# Separator-C.net
KiCad netlist of a schematic drawn in EAGLE
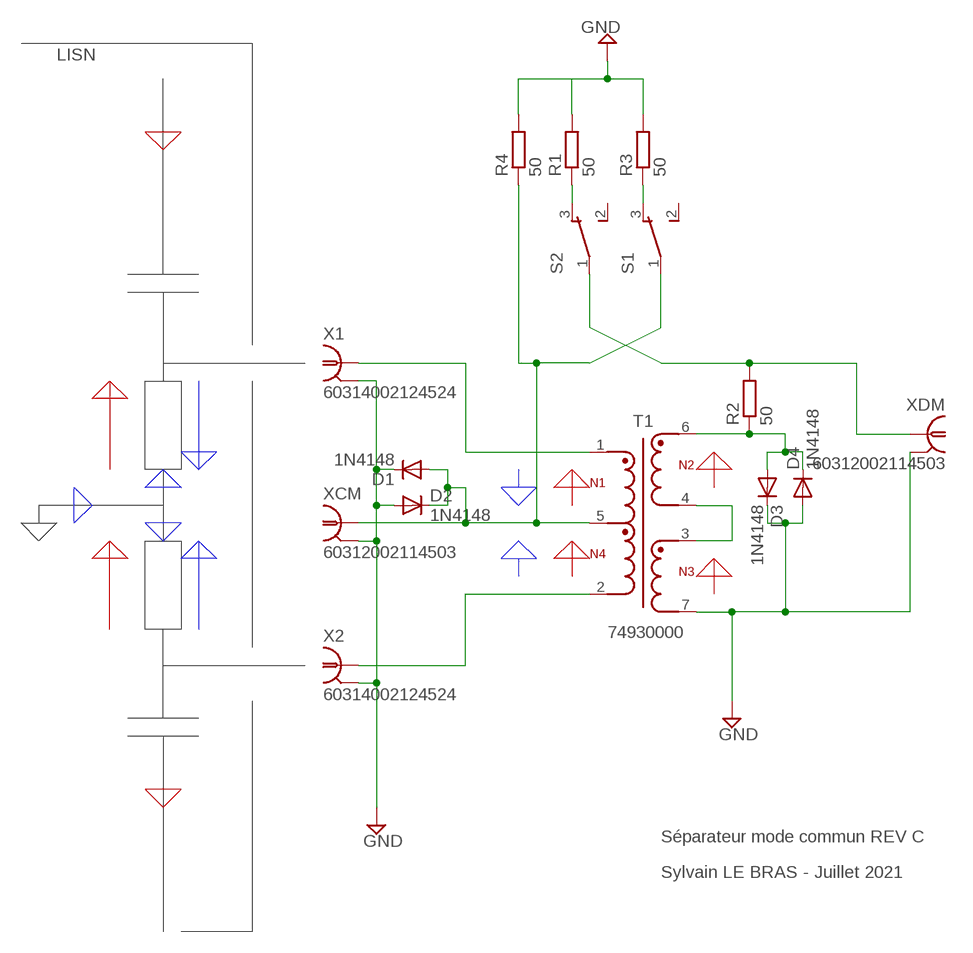
[diagram p0: schematic, sheet 1]

(export (version "E")
  (design (tool "Eeschema 10.0.6"))
  (components
    (comp (ref "D1")
      (value "1N4148")
      (footprint "eagle-import:SOD123")
      (libsource (lib "eagle-import") (part "DIODE-SOD123"))
    )
    (comp (ref "D2")
      (value "1N4148")
      (footprint "eagle-import:SOD123")
      (libsource (lib "eagle-import") (part "DIODE-SOD123"))
    )
    (comp (ref "D3")
      (value "1N4148")
      (footprint "eagle-import:SOD123")
      (libsource (lib "eagle-import") (part "DIODE-SOD123"))
    )
    (comp (ref "D4")
      (value "1N4148")
      (footprint "eagle-import:SOD123")
      (libsource (lib "eagle-import") (part "DIODE-SOD123"))
    )
    (comp (ref "R1")
      (value "50")
      (footprint "eagle-import:R0805")
      (libsource (lib "eagle-import") (part "R-EU_R0805"))
    )
    (comp (ref "R2")
      (value "50")
      (footprint "eagle-import:R0805")
      (libsource (lib "eagle-import") (part "R-EU_R0805"))
    )
    (comp (ref "R3")
      (value "50")
      (footprint "eagle-import:R0805")
      (libsource (lib "eagle-import") (part "R-EU_R0805"))
    )
    (comp (ref "R4")
      (value "50")
      (footprint "eagle-import:R0805")
      (libsource (lib "eagle-import") (part "R-EU_R0805"))
    )
    (comp (ref "S1")
      (value "450301014042")
      (footprint "eagle-import:450301014042")
      (libsource (lib "eagle-import") (part "450301014042"))
    )
    (comp (ref "S2")
      (value "450301014042")
      (footprint "eagle-import:450301014042")
      (libsource (lib "eagle-import") (part "450301014042"))
    )
    (comp (ref "T1")
      (value "74930000")
      (footprint "eagle-import:WE-STST_74930000")
      (libsource (lib "eagle-import") (part "WE-STST_4532_74930000"))
    )
    (comp (ref "X1")
      (value "60314002124524")
      (footprint "eagle-import:LTI-SASF54GT")
      (libsource (lib "eagle-import") (part "LTI-SASF54GT"))
    )
    (comp (ref "X2")
      (value "60314002124524")
      (footprint "eagle-import:LTI-SASF54GT")
      (libsource (lib "eagle-import") (part "LTI-SASF54GT"))
    )
    (comp (ref "XCM")
      (value "60312002114503")
      (footprint "eagle-import:LTI-SASF54GT")
      (libsource (lib "eagle-import") (part "LTI-SASF54GT"))
    )
    (comp (ref "XDM")
      (value "60312002114503")
      (footprint "eagle-import:LTI-SASF54GT")
      (libsource (lib "eagle-import") (part "LTI-SASF54GT"))
    )
  )
  (nets
    (net (code "1") (name "GND") (class "Default")
      (node (ref "D1") (pin "C") (pinfunction "C_C") (pintype "passive"))
      (node (ref "D2") (pin "A") (pinfunction "A_A") (pintype "passive"))
      (node (ref "D3") (pin "C") (pinfunction "C_C") (pintype "passive"))
      (node (ref "D4") (pin "A") (pinfunction "A_A") (pintype "passive"))
      (node (ref "R1") (pin "2") (pinfunction "2_2") (pintype "passive"))
      (node (ref "R3") (pin "2") (pinfunction "2_2") (pintype "passive"))
      (node (ref "R4") (pin "2") (pinfunction "2_2") (pintype "passive"))
      (node (ref "T1") (pin "7") (pinfunction "7_7") (pintype "passive"))
      (node (ref "X1") (pin "2") (pinfunction "GND_2") (pintype "power_in"))
      (node (ref "X2") (pin "2") (pinfunction "GND_2") (pintype "power_in"))
      (node (ref "XCM") (pin "2") (pinfunction "GND_2") (pintype "power_in"))
      (node (ref "XDM") (pin "2") (pinfunction "GND_2") (pintype "power_in"))
    )
    (net (code "2") (name "Net-(D1-PadA)") (class "Default")
      (node (ref "D1") (pin "A") (pinfunction "A_A") (pintype "passive"))
      (node (ref "D2") (pin "C") (pinfunction "C_C") (pintype "passive"))
      (node (ref "R4") (pin "1") (pinfunction "1_1") (pintype "passive"))
      (node (ref "S1") (pin "1") (pinfunction "1_1") (pintype "passive"))
      (node (ref "T1") (pin "5") (pinfunction "5_5") (pintype "passive"))
      (node (ref "XCM") (pin "1") (pinfunction "1_1") (pintype "passive"))
    )
    (net (code "3") (name "Net-(D3-PadA)") (class "Default")
      (node (ref "D3") (pin "A") (pinfunction "A_A") (pintype "passive"))
      (node (ref "D4") (pin "C") (pinfunction "C_C") (pintype "passive"))
      (node (ref "R2") (pin "1") (pinfunction "1_1") (pintype "passive"))
      (node (ref "T1") (pin "6") (pinfunction "6_6") (pintype "passive"))
    )
    (net (code "4") (name "Net-(R1-Pad1)") (class "Default")
      (node (ref "R1") (pin "1") (pinfunction "1_1") (pintype "passive"))
      (node (ref "S2") (pin "3") (pinfunction "3_3") (pintype "passive"))
    )
    (net (code "5") (name "Net-(R2-Pad2)") (class "Default")
      (node (ref "R2") (pin "2") (pinfunction "2_2") (pintype "passive"))
      (node (ref "S2") (pin "1") (pinfunction "1_1") (pintype "passive"))
      (node (ref "XDM") (pin "1") (pinfunction "1_1") (pintype "passive"))
    )
    (net (code "6") (name "Net-(R3-Pad1)") (class "Default")
      (node (ref "R3") (pin "1") (pinfunction "1_1") (pintype "passive"))
      (node (ref "S1") (pin "3") (pinfunction "3_3") (pintype "passive"))
    )
    (net (code "7") (name "Net-(T1-Pad1)") (class "Default")
      (node (ref "T1") (pin "1") (pinfunction "1_1") (pintype "passive"))
      (node (ref "X1") (pin "1") (pinfunction "1_1") (pintype "passive"))
    )
    (net (code "8") (name "Net-(T1-Pad2)") (class "Default")
      (node (ref "T1") (pin "2") (pinfunction "2_2") (pintype "passive"))
      (node (ref "X2") (pin "1") (pinfunction "1_1") (pintype "passive"))
    )
    (net (code "9") (name "Net-(T1-Pad3)") (class "Default")
      (node (ref "T1") (pin "3") (pinfunction "3_3") (pintype "passive"))
      (node (ref "T1") (pin "4") (pinfunction "4_4") (pintype "passive"))
    )
    (net (code "10") (name "unconnected-(S1-Pad2)") (class "Default")
      (node (ref "S1") (pin "2") (pinfunction "2_2") (pintype "passive"))
    )
    (net (code "11") (name "unconnected-(S2-Pad2)") (class "Default")
      (node (ref "S2") (pin "2") (pinfunction "2_2") (pintype "passive"))
    )
  )
)
